# esp8266.net
KiCad netlist of a schematic drawn in Altium Designer
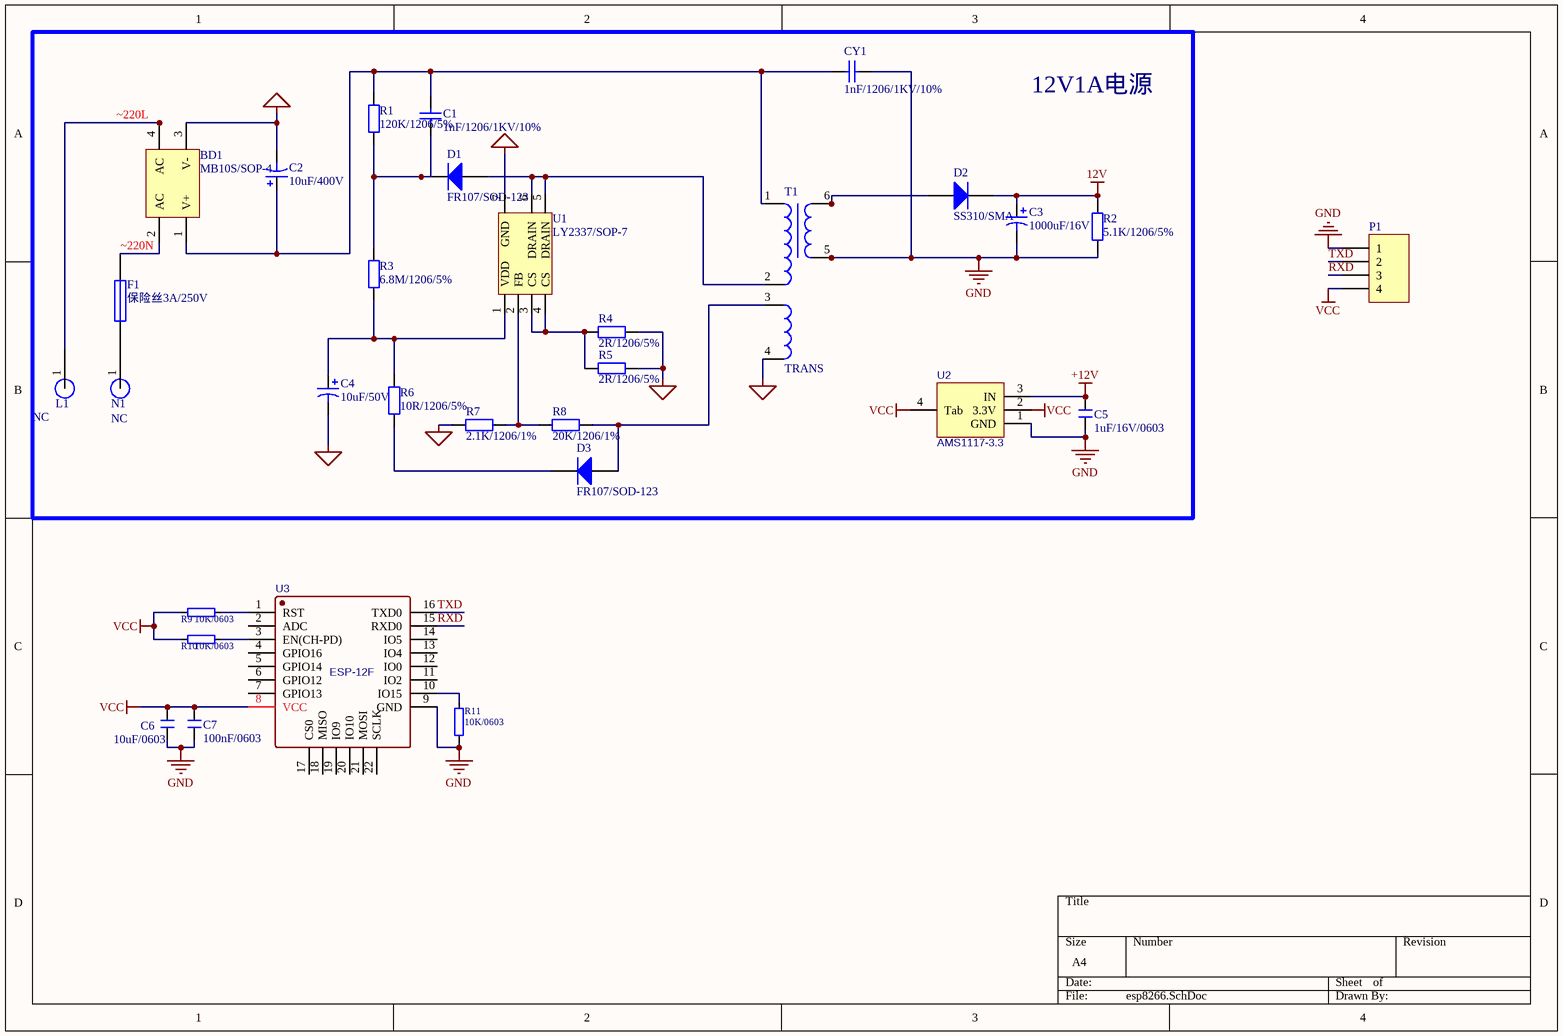
[diagram p0: esp8266.SchDoc]

(export (version "E")
  (design (tool "Eeschema 10.0.6"))
  (components
    (comp (ref "BD1")
      (value "MB10S/SOP-4")
      (footprint "MBL10S")
      (description "整流桥 MB10S/SOP-4")
      (fields (field (name "PUBLISHER") "Altium Limited"))
      (libsource (lib "Miscellaneous Devices") (part "Bridge2"))
    )
    (comp (ref "C1")
      (value "1nF/1206/1KV/10%")
      (footprint "C1206")
      (description "1nF/1206/50V/10%")
      (fields (field (name "PUBLISHER") "Altium Limited"))
      (libsource (lib "Miscellaneous Devices") (part "Cap"))
    )
    (comp (ref "C2")
      (value "10uF/400V")
      (footprint "400V/10uF 8*12mm")
      (description "直插电解电容10uF/400V")
      (fields (field (name "PUBLISHER") "Altium Limited"))
      (libsource (lib "Miscellaneous Devices") (part "Cap Pol1"))
    )
    (comp (ref "C3")
      (value "1000uF/16V")
      (footprint "16V/1000uF 8*16mm -2")
      (description "直插电解电容1000uF/16V")
      (fields (field (name "PUBLISHER") "Altium Limited"))
      (libsource (lib "Miscellaneous Devices") (part "Cap Pol1"))
    )
    (comp (ref "C4")
      (value "10uF/50V")
      (footprint "50V/10uF")
      (description "直插电解电容10uF/50V")
      (fields (field (name "PUBLISHER") "Altium Limited"))
      (libsource (lib "Miscellaneous Devices") (part "Cap Pol1"))
    )
    (comp (ref "C5") (value "1uF/16V/0603") (footprint "C0603") (libsource (lib "esp8266") (part "CAP")))
    (comp (ref "C6") (value "10uF/0603") (footprint "C0603") (libsource (lib "esp8266") (part "CAP")))
    (comp (ref "C7") (value "100nF/0603") (footprint "C0603") (libsource (lib "esp8266") (part "CAP")))
    (comp (ref "CY1")
      (value "1nF/1206/1KV/10%")
      (footprint "C1206")
      (description "1nF/1206/50V/10%")
      (fields (field (name "PUBLISHER") "Altium Limited"))
      (libsource (lib "Miscellaneous Devices") (part "Cap"))
    )
    (comp (ref "D1")
      (value "FR107/SOD-123")
      (footprint "SOD123")
      (description "快恢复二极管 FR107 封装SOD-123")
      (fields (field (name "PUBLISHER") "Altium Limited"))
      (libsource (lib "Miscellaneous Devices") (part "Diode"))
    )
    (comp (ref "D2")
      (value "SS310/SMA")
      (footprint "SMA")
      (description "肖特基二极管 SS310/封装 SMA")
      (fields (field (name "PUBLISHER") "Altium Limited"))
      (libsource (lib "Miscellaneous Devices") (part "Diode"))
    )
    (comp (ref "D3")
      (value "FR107/SOD-123")
      (footprint "SOD123")
      (description "快恢复二极管 FR107 封装SOD-123")
      (fields (field (name "PUBLISHER") "Altium Limited"))
      (libsource (lib "Miscellaneous Devices") (part "Diode"))
    )
    (comp (ref "F1")
      (value "保险丝3A/250V")
      (footprint "方块保险丝4*8mm")
      (fields (field (name "PUBLISHER") "Altium Limited"))
      (libsource (lib "Miscellaneous Devices") (part "Fuse 1"))
    )
    (comp (ref "L1")
      (value "NC")
      (footprint "PAD")
      (description "焊接点")
      (libsource (lib "TS_2A") (part "Welding-hole"))
    )
    (comp (ref "N1")
      (value "NC")
      (footprint "PAD")
      (description "焊接点")
      (libsource (lib "TS_2A") (part "Welding-hole"))
    )
    (comp (ref "P1")
      (value "Header 4")
      (footprint "HDR1X4")
      (description "Header, 4-Pin")
      (fields (field (name "PUBLISHER") "Altium Limited"))
      (libsource (lib "Miscellaneous Connectors") (part "Header 4"))
    )
    (comp (ref "R1")
      (value "120K/1206/5%")
      (footprint "R1206")
      (description "Resistor 120K/1206/5%")
      (fields (field (name "PUBLISHER") "Altium Limited"))
      (libsource (lib "") (part "Res2_1"))
    )
    (comp (ref "R2")
      (value "5.1K/1206/5%")
      (footprint "R1206")
      (description "Resistor 5.1K/1206/5%")
      (fields (field (name "PUBLISHER") "Altium Limited"))
      (libsource (lib "") (part "Res2_1"))
    )
    (comp (ref "R3")
      (value "6.8M/1206/5%")
      (footprint "R1206")
      (description "Resistor 6.8M/1206/5%  6.8兆欧姆")
      (fields (field (name "PUBLISHER") "Altium Limited"))
      (libsource (lib "") (part "Res2_1"))
    )
    (comp (ref "R4")
      (value "2R/1206/5%")
      (footprint "R1206")
      (description "Resistor 2R/1206/5%")
      (fields (field (name "PUBLISHER") "Altium Limited"))
      (libsource (lib "Miscellaneous Devices") (part "Res2"))
    )
    (comp (ref "R5")
      (value "2R/1206/5%")
      (footprint "R1206")
      (description "Resistor 2R/1206/5%")
      (fields (field (name "PUBLISHER") "Altium Limited"))
      (libsource (lib "Miscellaneous Devices") (part "Res2"))
    )
    (comp (ref "R6")
      (value "10R/1206/5%")
      (footprint "R1206")
      (description "Resistor 10R/1206/5%")
      (fields (field (name "PUBLISHER") "Altium Limited"))
      (libsource (lib "") (part "Res2_2"))
    )
    (comp (ref "R7")
      (value "2.1K/1206/1%")
      (footprint "R1206")
      (description "Resistor 2.1K/1206/1%")
      (fields (field (name "PUBLISHER") "Altium Limited"))
      (libsource (lib "Miscellaneous Devices") (part "Res2"))
    )
    (comp (ref "R8")
      (value "20K/1206/1%")
      (footprint "R1206")
      (description "Resistor 20K/1206/1%")
      (fields (field (name "PUBLISHER") "Altium Limited"))
      (libsource (lib "Miscellaneous Devices") (part "Res2"))
    )
    (comp (ref "R9") (value "10K/0603") (footprint "R0603") (libsource (lib "esp8266") (part "RES")))
    (comp (ref "R10") (value "10K/0603") (footprint "R0603") (libsource (lib "esp8266") (part "RES")))
    (comp (ref "R11") (value "10K/0603") (footprint "R0603") (libsource (lib "esp8266") (part "RES")))
    (comp (ref "T1")
      (value "TRANS")
      (footprint "EPC-17_2")
      (description "变压器")
      (libsource (lib "Schlib1") (part "TRANS"))
    )
    (comp (ref "U1")
      (value "LY2337/SOP-7")
      (footprint "SOP-7")
      (libsource (lib "Schlib1") (part "Component_1"))
    )
    (comp (ref "U2")
      (value "AMS1117-3.3")
      (footprint "SOT-223_L6.5-W3.5-P2.30-LS7.0-BR")
      (fields (field (name "BOM_SUPPLIER PART") "C165482") (field (name "CONTRIBUTOR") "LCSC"))
      (libsource (lib "esp8266") (part "AMS1117-3.3"))
    )
    (comp (ref "U3")
      (value "ESP-12F")
      (footprint "WIFIM-SMD_ESP-12F-ESP8266MOD")
      (fields
        (field (name "BOM_MANUFACTURER PART") "ESP-12F(ESP8266MOD)")
        (field (name "BOM_SUPPLIER PART") "C82891")
      )
      (libsource (lib "esp8266") (part "ESP-12F(ESP8266MOD)"))
    )
  )
  (nets
    (net (code "1") (name "+12V") (class "Default")
      (node (ref "C5") (pin "2") (pinfunction "2_2") (pintype "passive"))
      (node (ref "U2") (pin "3") (pinfunction "IN_3") (pintype "passive"))
    )
    (net (code "2") (name "/RXD") (class "Default")
      (node (ref "P1") (pin "3") (pinfunction "3_3") (pintype "passive"))
      (node (ref "U3") (pin "15") (pinfunction "RXD0_15") (pintype "passive"))
    )
    (net (code "3") (name "/TXD") (class "Default")
      (node (ref "P1") (pin "2") (pinfunction "2_2") (pintype "passive"))
      (node (ref "U3") (pin "16") (pinfunction "TXD0_16") (pintype "passive"))
    )
    (net (code "4") (name "/~220L") (class "Default")
      (node (ref "BD1") (pin "4") (pinfunction "AC_4") (pintype "passive"))
      (node (ref "L1") (pin "1") (pinfunction "1_1") (pintype "passive"))
    )
    (net (code "5") (name "/~220N") (class "Default")
      (node (ref "BD1") (pin "2") (pinfunction "AC_2") (pintype "passive"))
      (node (ref "F1") (pin "2") (pinfunction "2_2") (pintype "passive"))
    )
    (net (code "6") (name "12V") (class "Default")
      (node (ref "C3") (pin "1") (pinfunction "1_1") (pintype "passive"))
      (node (ref "D2") (pin "2") (pinfunction "K_2") (pintype "passive"))
      (node (ref "R2") (pin "2") (pinfunction "2_2") (pintype "passive"))
    )
    (net (code "7") (name "AGND") (class "Default")
      (node (ref "BD1") (pin "3") (pinfunction "V-_3") (pintype "passive"))
      (node (ref "C2") (pin "2") (pinfunction "2_2") (pintype "passive"))
      (node (ref "C4") (pin "2") (pinfunction "2_2") (pintype "passive"))
      (node (ref "R4") (pin "2") (pinfunction "2_2") (pintype "passive"))
      (node (ref "R5") (pin "2") (pinfunction "2_2") (pintype "passive"))
      (node (ref "R7") (pin "1") (pinfunction "1_1") (pintype "passive"))
      (node (ref "T1") (pin "4") (pinfunction "5_4") (pintype "passive"))
      (node (ref "U1") (pin "7") (pinfunction "GND_7") (pintype "passive"))
    )
    (net (code "8") (name "GND") (class "Default")
      (node (ref "C3") (pin "2") (pinfunction "2_2") (pintype "passive"))
      (node (ref "C5") (pin "1") (pinfunction "1_1") (pintype "passive"))
      (node (ref "C6") (pin "1") (pinfunction "1_1") (pintype "passive"))
      (node (ref "C7") (pin "1") (pinfunction "1_1") (pintype "passive"))
      (node (ref "CY1") (pin "2") (pinfunction "2_2") (pintype "passive"))
      (node (ref "P1") (pin "1") (pinfunction "1_1") (pintype "passive"))
      (node (ref "R11") (pin "1") (pinfunction "1_1") (pintype "passive"))
      (node (ref "R2") (pin "1") (pinfunction "1_1") (pintype "passive"))
      (node (ref "T1") (pin "5") (pinfunction "5_5") (pintype "passive"))
      (node (ref "U2") (pin "1") (pinfunction "GND_1") (pintype "passive"))
      (node (ref "U3") (pin "9") (pinfunction "GND_9") (pintype "passive"))
    )
    (net (code "9") (name "Net-(BD1-V+)") (class "Default")
      (node (ref "BD1") (pin "1") (pinfunction "V+_1") (pintype "passive"))
      (node (ref "C1") (pin "2") (pinfunction "2_2") (pintype "passive"))
      (node (ref "C2") (pin "1") (pinfunction "1_1") (pintype "passive"))
      (node (ref "CY1") (pin "1") (pinfunction "1_1") (pintype "passive"))
      (node (ref "R1") (pin "2") (pinfunction "2_2") (pintype "passive"))
      (node (ref "T1") (pin "1") (pinfunction "1_1") (pintype "passive"))
    )
    (net (code "10") (name "Net-(D1-A)") (class "Default")
      (node (ref "D1") (pin "1") (pinfunction "A_1") (pintype "passive"))
      (node (ref "T1") (pin "2") (pinfunction "2_2") (pintype "passive"))
      (node (ref "U1") (pin "5") (pinfunction "DRAIN_5") (pintype "passive"))
      (node (ref "U1") (pin "6") (pinfunction "DRAIN_6") (pintype "passive"))
    )
    (net (code "11") (name "Net-(D1-K)") (class "Default")
      (node (ref "C1") (pin "1") (pinfunction "1_1") (pintype "passive"))
      (node (ref "D1") (pin "2") (pinfunction "K_2") (pintype "passive"))
      (node (ref "R1") (pin "1") (pinfunction "1_1") (pintype "passive"))
      (node (ref "R3") (pin "2") (pinfunction "2_2") (pintype "passive"))
    )
    (net (code "12") (name "Net-(D2-A)") (class "Default")
      (node (ref "D2") (pin "1") (pinfunction "A_1") (pintype "passive"))
      (node (ref "T1") (pin "6") (pinfunction "6_6") (pintype "passive"))
    )
    (net (code "13") (name "Net-(D3-A)") (class "Default")
      (node (ref "D3") (pin "1") (pinfunction "A_1") (pintype "passive"))
      (node (ref "R8") (pin "2") (pinfunction "2_2") (pintype "passive"))
      (node (ref "T1") (pin "3") (pinfunction "3_3") (pintype "passive"))
    )
    (net (code "14") (name "Net-(D3-K)") (class "Default")
      (node (ref "D3") (pin "2") (pinfunction "K_2") (pintype "passive"))
      (node (ref "R6") (pin "2") (pinfunction "2_2") (pintype "passive"))
    )
    (net (code "15") (name "Net-(F1-Pad1)") (class "Default")
      (node (ref "F1") (pin "1") (pinfunction "1_1") (pintype "passive"))
      (node (ref "N1") (pin "1") (pinfunction "1_1") (pintype "passive"))
    )
    (net (code "16") (name "Net-(R4-Pad1)") (class "Default")
      (node (ref "R4") (pin "1") (pinfunction "1_1") (pintype "passive"))
      (node (ref "R5") (pin "1") (pinfunction "1_1") (pintype "passive"))
      (node (ref "U1") (pin "3") (pinfunction "CS_3") (pintype "passive"))
      (node (ref "U1") (pin "4") (pinfunction "CS_4") (pintype "passive"))
    )
    (net (code "17") (name "Net-(U1-FB)") (class "Default")
      (node (ref "R7") (pin "2") (pinfunction "2_2") (pintype "passive"))
      (node (ref "R8") (pin "1") (pinfunction "1_1") (pintype "passive"))
      (node (ref "U1") (pin "2") (pinfunction "FB_2") (pintype "passive"))
    )
    (net (code "18") (name "Net-(U1-VDD)") (class "Default")
      (node (ref "C4") (pin "1") (pinfunction "1_1") (pintype "passive"))
      (node (ref "R3") (pin "1") (pinfunction "1_1") (pintype "passive"))
      (node (ref "R6") (pin "1") (pinfunction "1_1") (pintype "passive"))
      (node (ref "U1") (pin "1") (pinfunction "VDD_1") (pintype "passive"))
    )
    (net (code "19") (name "Net-(U3-EN(CH-PD))") (class "Default")
      (node (ref "R10") (pin "2") (pinfunction "2_2") (pintype "passive"))
      (node (ref "U3") (pin "3") (pinfunction "EN(CH-PD)_3") (pintype "passive"))
    )
    (net (code "20") (name "Net-(U3-IO15)") (class "Default")
      (node (ref "R11") (pin "2") (pinfunction "2_2") (pintype "passive"))
      (node (ref "U3") (pin "10") (pinfunction "IO15_10") (pintype "passive"))
    )
    (net (code "21") (name "Net-(U3-RST)") (class "Default")
      (node (ref "R9") (pin "2") (pinfunction "2_2") (pintype "passive"))
      (node (ref "U3") (pin "1") (pinfunction "RST_1") (pintype "passive"))
    )
    (net (code "22") (name "VCC") (class "Default")
      (node (ref "C6") (pin "2") (pinfunction "2_2") (pintype "passive"))
      (node (ref "C7") (pin "2") (pinfunction "2_2") (pintype "passive"))
      (node (ref "P1") (pin "4") (pinfunction "4_4") (pintype "passive"))
      (node (ref "R10") (pin "1") (pinfunction "1_1") (pintype "passive"))
      (node (ref "R9") (pin "1") (pinfunction "1_1") (pintype "passive"))
      (node (ref "U2") (pin "2") (pinfunction "3.3V_2") (pintype "passive"))
      (node (ref "U2") (pin "4") (pinfunction "Tab_4") (pintype "passive"))
      (node (ref "U3") (pin "8") (pinfunction "VCC_8") (pintype "passive"))
    )
    (net (code "23") (name "unconnected-(U3-ADC-Pad2)") (class "Default")
      (node (ref "U3") (pin "2") (pinfunction "ADC_2") (pintype "passive"))
    )
    (net (code "24") (name "unconnected-(U3-CS0-Pad17)") (class "Default")
      (node (ref "U3") (pin "17") (pinfunction "CS0_17") (pintype "passive"))
    )
    (net (code "25") (name "unconnected-(U3-GPIO12-Pad6)") (class "Default")
      (node (ref "U3") (pin "6") (pinfunction "GPIO12_6") (pintype "passive"))
    )
    (net (code "26") (name "unconnected-(U3-GPIO13-Pad7)") (class "Default")
      (node (ref "U3") (pin "7") (pinfunction "GPIO13_7") (pintype "passive"))
    )
    (net (code "27") (name "unconnected-(U3-GPIO14-Pad5)") (class "Default")
      (node (ref "U3") (pin "5") (pinfunction "GPIO14_5") (pintype "passive"))
    )
    (net (code "28") (name "unconnected-(U3-GPIO16-Pad4)") (class "Default")
      (node (ref "U3") (pin "4") (pinfunction "GPIO16_4") (pintype "passive"))
    )
    (net (code "29") (name "unconnected-(U3-IO0-Pad12)") (class "Default")
      (node (ref "U3") (pin "12") (pinfunction "IO0_12") (pintype "passive"))
    )
    (net (code "30") (name "unconnected-(U3-IO2-Pad11)") (class "Default")
      (node (ref "U3") (pin "11") (pinfunction "IO2_11") (pintype "passive"))
    )
    (net (code "31") (name "unconnected-(U3-IO4-Pad13)") (class "Default")
      (node (ref "U3") (pin "13") (pinfunction "IO4_13") (pintype "passive"))
    )
    (net (code "32") (name "unconnected-(U3-IO5-Pad14)") (class "Default")
      (node (ref "U3") (pin "14") (pinfunction "IO5_14") (pintype "passive"))
    )
    (net (code "33") (name "unconnected-(U3-IO9-Pad19)") (class "Default")
      (node (ref "U3") (pin "19") (pinfunction "IO9_19") (pintype "passive"))
    )
    (net (code "34") (name "unconnected-(U3-IO10-Pad20)") (class "Default")
      (node (ref "U3") (pin "20") (pinfunction "IO10_20") (pintype "passive"))
    )
    (net (code "35") (name "unconnected-(U3-MISO-Pad18)") (class "Default")
      (node (ref "U3") (pin "18") (pinfunction "MISO_18") (pintype "passive"))
    )
    (net (code "36") (name "unconnected-(U3-MOSI-Pad21)") (class "Default")
      (node (ref "U3") (pin "21") (pinfunction "MOSI_21") (pintype "passive"))
    )
    (net (code "37") (name "unconnected-(U3-SCLK-Pad22)") (class "Default")
      (node (ref "U3") (pin "22") (pinfunction "SCLK_22") (pintype "passive"))
    )
  )
)
